# USB_RS485_Board.net
KiCad netlist of a schematic drawn in Altium Designer
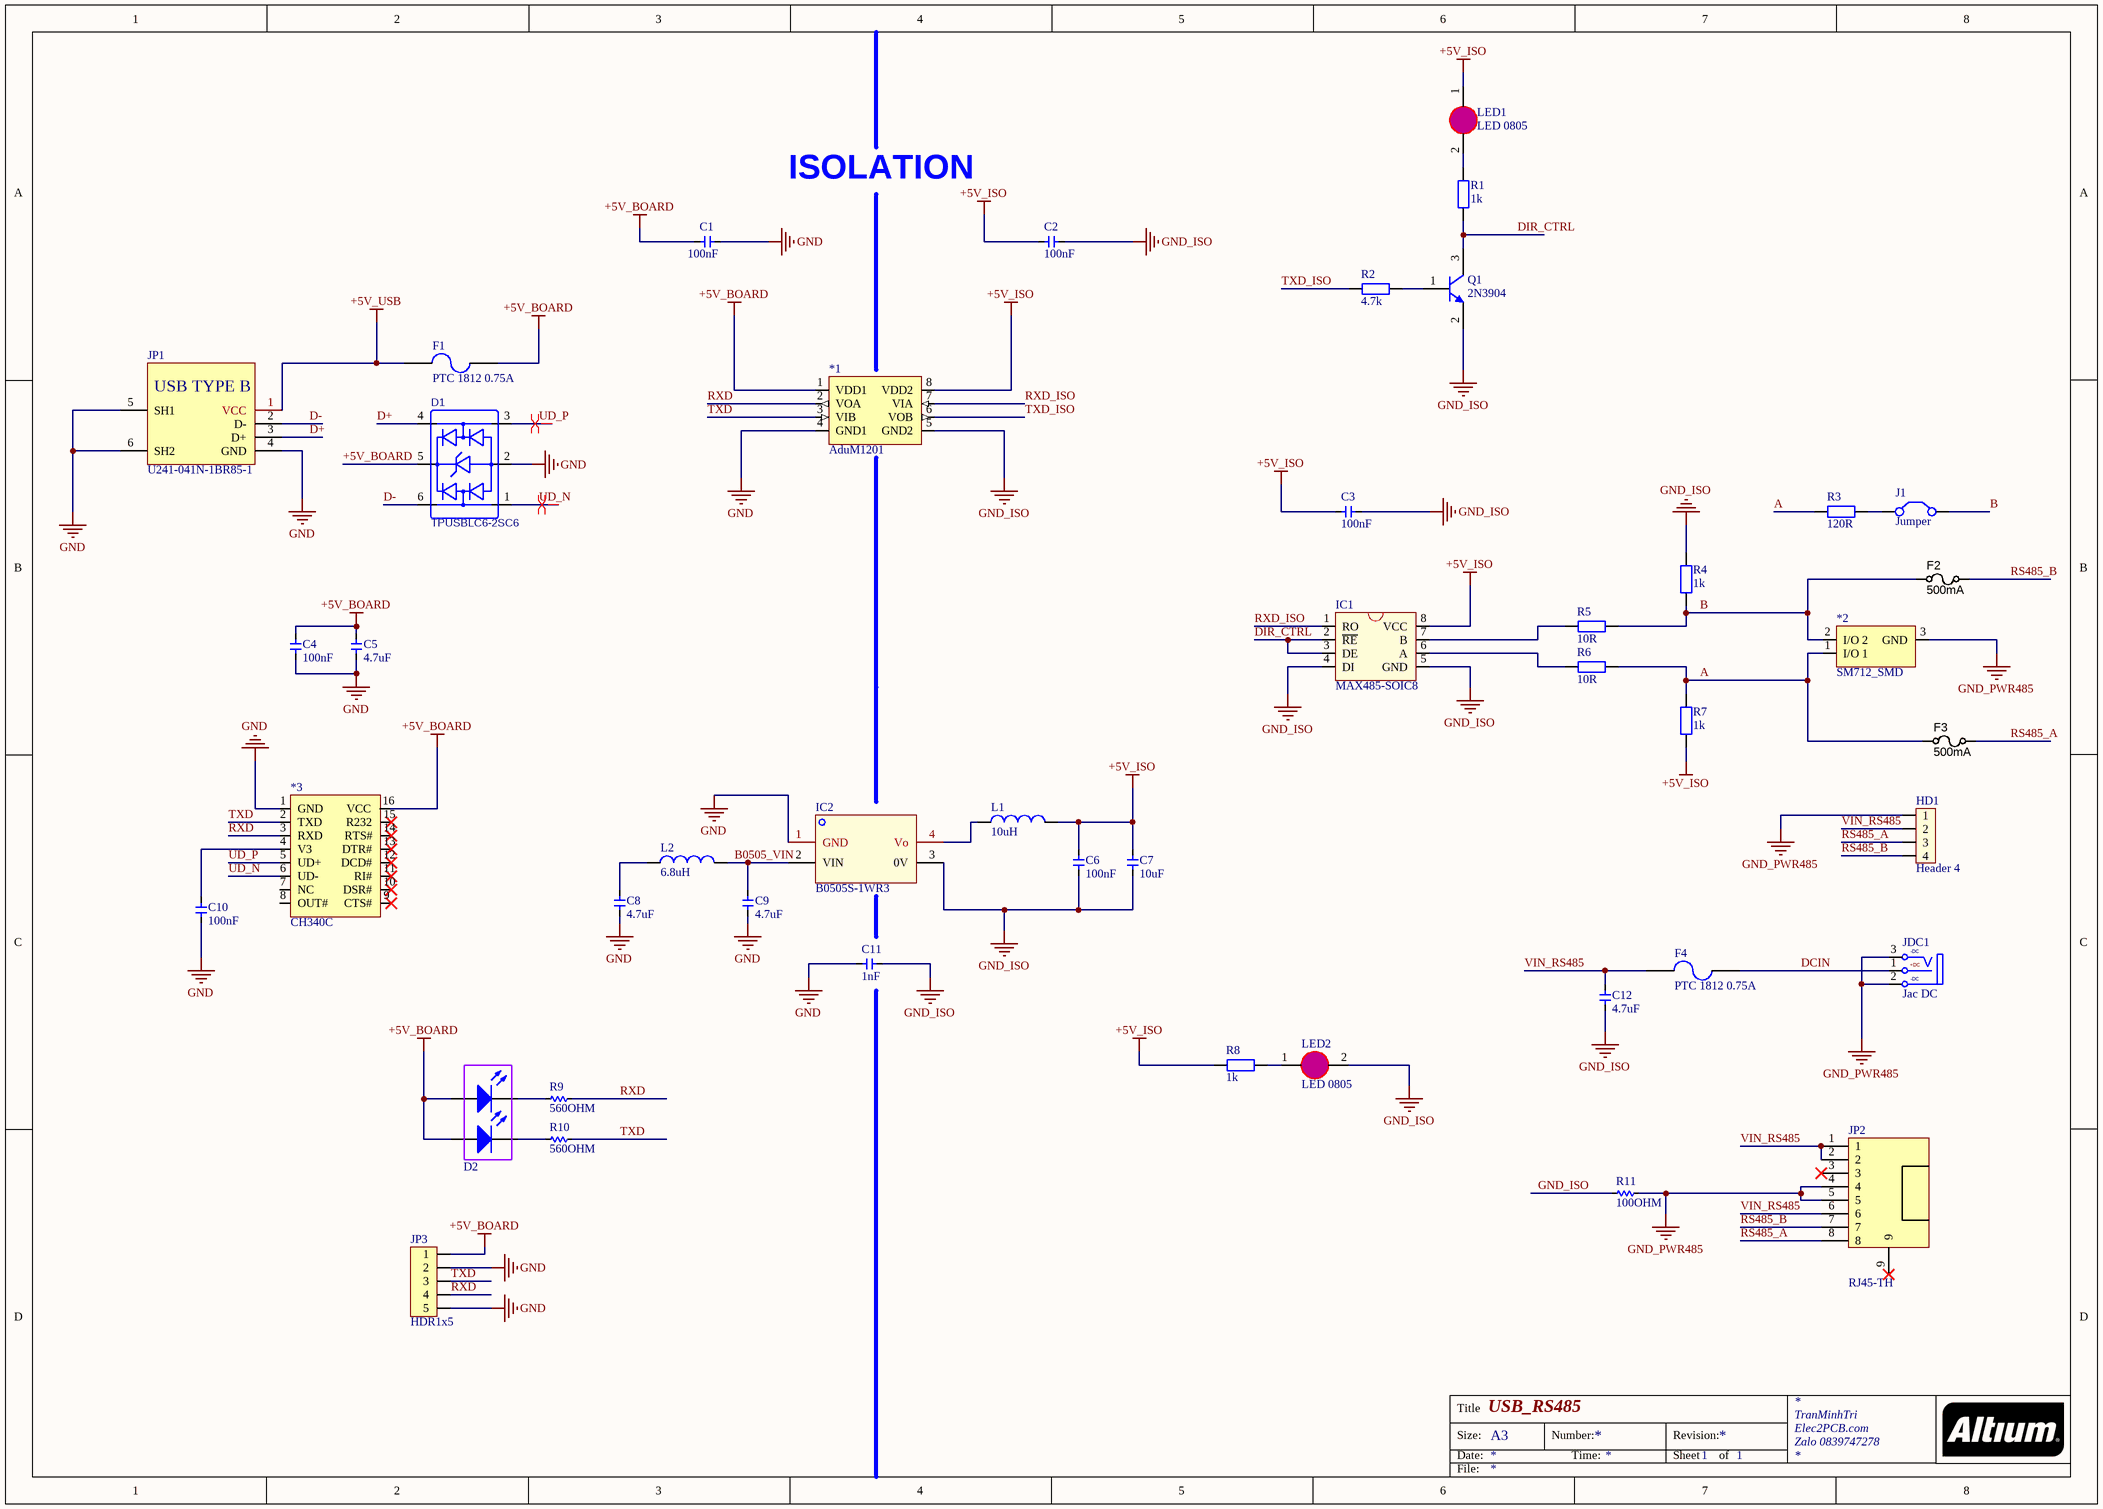
[diagram p0: USB_RS485_Board.SchDoc]

(export (version "E")
  (design (tool "Eeschema 10.0.6"))
  (components
    (comp (ref "*1")
      (value "AduM1201")
      (footprint "THU VIEN PCB:SO-8")
      (libsource (lib "lpson") (part "AduM1201"))
    )
    (comp (ref "*2")
      (value "SM712_SMD")
      (footprint "my Library:SOT23-3")
      (libsource (lib "lpson") (part "SM712_SMD"))
    )
    (comp (ref "*3")
      (value "CH340C")
      (footprint "THU VIEN PCB:SOP16")
      (libsource (lib "lpson") (part "CH340C dip"))
    )
    (comp (ref "C1")
      (value "100nF")
      (footprint "my Library:C_0603")
      (description "100nF 50V X7R ±10% 0603 Multilayer Ceramic Capacitors MLCC - SMD/SMT ROHS")
      (fields
        (field (name "MANUFACTURER") "YAGEO")
        (field (name "MANUFACTURER PART NUMBER") "CC0603KRX7R9BB104")
      )
      (libsource (lib "USB to RS485 ISO - ISO3088") (part "CC0603KRX7R9BB104"))
    )
    (comp (ref "C2")
      (value "100nF")
      (footprint "my Library:C_0603")
      (description "100nF 50V X7R ±10% 0603 Multilayer Ceramic Capacitors MLCC - SMD/SMT ROHS")
      (fields
        (field (name "MANUFACTURER") "YAGEO")
        (field (name "MANUFACTURER PART NUMBER") "CC0603KRX7R9BB104")
      )
      (libsource (lib "USB to RS485 ISO - ISO3088") (part "CC0603KRX7R9BB104"))
    )
    (comp (ref "C3")
      (value "100nF")
      (footprint "my Library:C_0603")
      (description "100nF 50V X7R ±10% 0603 Multilayer Ceramic Capacitors MLCC - SMD/SMT ROHS")
      (fields
        (field (name "MANUFACTURER") "YAGEO")
        (field (name "MANUFACTURER PART NUMBER") "CC0603KRX7R9BB104")
      )
      (libsource (lib "USB to RS485 ISO - ISO3088") (part "CC0603KRX7R9BB104"))
    )
    (comp (ref "C4")
      (value "100nF")
      (footprint "my Library:C_0603")
      (description "100nF 50V X7R ±10% 0603 Multilayer Ceramic Capacitors MLCC - SMD/SMT ROHS")
      (fields
        (field (name "MANUFACTURER") "YAGEO")
        (field (name "MANUFACTURER PART NUMBER") "CC0603KRX7R9BB104")
      )
      (libsource (lib "USB to RS485 ISO - ISO3088") (part "CC0603KRX7R9BB104"))
    )
    (comp (ref "C5")
      (value "4.7uF")
      (footprint "my Library:C_1206")
      (description "4.7uF 50V X7R ±10% 1206 Multilayer Ceramic Capacitors MLCC - SMD/SMT ROHS")
      (fields
        (field (name "MANUFACTURER") "FH(Guangdong Fenghua Advanced Tech)")
        (field (name "MANUFACTURER PART NUMBER") "1206B475K500NT")
      )
      (libsource (lib "USB to RS485 ISO - ISO3088") (part "1206B475K500NT"))
    )
    (comp (ref "C6")
      (value "100nF")
      (footprint "my Library:C_0603")
      (description "4.7uF 50V X7R ±10% 1206 Multilayer Ceramic Capacitors MLCC - SMD/SMT ROHS")
      (fields
        (field (name "MANUFACTURER") "FH(Guangdong Fenghua Advanced Tech)")
        (field (name "MANUFACTURER PART NUMBER") "1206B475K500NT")
      )
      (libsource (lib "USB to RS485 ISO - ISO3088") (part "1206B475K500NT"))
    )
    (comp (ref "C7")
      (value "10uF")
      (footprint "my Library:C_1206")
      (description "4.7uF 50V X7R ±10% 1206 Multilayer Ceramic Capacitors MLCC - SMD/SMT ROHS")
      (fields
        (field (name "MANUFACTURER") "FH(Guangdong Fenghua Advanced Tech)")
        (field (name "MANUFACTURER PART NUMBER") "1206B475K500NT")
      )
      (libsource (lib "USB to RS485 ISO - ISO3088") (part "1206B475K500NT"))
    )
    (comp (ref "C8")
      (value "4.7uF")
      (footprint "my Library:C_1206")
      (description "4.7uF 50V X7R ±10% 1206 Multilayer Ceramic Capacitors MLCC - SMD/SMT ROHS")
      (fields
        (field (name "MANUFACTURER") "FH(Guangdong Fenghua Advanced Tech)")
        (field (name "MANUFACTURER PART NUMBER") "1206B475K500NT")
      )
      (libsource (lib "USB to RS485 ISO - ISO3088") (part "1206B475K500NT"))
    )
    (comp (ref "C9")
      (value "4.7uF")
      (footprint "my Library:C_1206")
      (description "4.7uF 50V X7R ±10% 1206 Multilayer Ceramic Capacitors MLCC - SMD/SMT ROHS")
      (fields
        (field (name "MANUFACTURER") "FH(Guangdong Fenghua Advanced Tech)")
        (field (name "MANUFACTURER PART NUMBER") "1206B475K500NT")
      )
      (libsource (lib "USB to RS485 ISO - ISO3088") (part "1206B475K500NT"))
    )
    (comp (ref "C10")
      (value "100nF")
      (footprint "my Library:C_0603")
      (description "100nF 50V X7R ±10% 0603 Multilayer Ceramic Capacitors MLCC - SMD/SMT ROHS")
      (fields
        (field (name "MANUFACTURER") "YAGEO")
        (field (name "MANUFACTURER PART NUMBER") "CC0603KRX7R9BB104")
      )
      (libsource (lib "USB to RS485 ISO - ISO3088") (part "CC0603KRX7R9BB104"))
    )
    (comp (ref "C11")
      (value "1nF")
      (footprint "C_1206")
      (description "1nF ±5% 1kV NP0 1206 Multilayer Ceramic Capacitors MLCC - SMD/SMT RoHS")
      (fields
        (field (name "MANUFACTURER") "YAGEO")
        (field (name "MANUFACTURER PART NUMBER") "CC1206JKNPOCBN102")
      )
      (libsource (lib "USB to RS485 ISO - ISO3088") (part "CC1206JKNPOCBN102"))
    )
    (comp (ref "C12")
      (value "4.7uF")
      (footprint "my Library:C_1206")
      (description "4.7uF 50V X7R ±10% 1206 Multilayer Ceramic Capacitors MLCC - SMD/SMT ROHS")
      (fields
        (field (name "MANUFACTURER") "FH(Guangdong Fenghua Advanced Tech)")
        (field (name "MANUFACTURER PART NUMBER") "1206B475K500NT")
      )
      (libsource (lib "USB to RS485 ISO - ISO3088") (part "1206B475K500NT"))
    )
    (comp (ref "D1")
      (value "TPUSBLC6-2SC6")
      (footprint "my Library:SOT-23-6_L2.9-W1.6-P0.95-LS2.8-BR")
      (description "ESD ROHS SOT23-6 DIODES")
      (fields (field (name "LCSC PART NUMBER") "C558442") (field (name "MANUFACTURER") "TECH PUBLIC"))
      (libsource (lib "lpson") (part "ESD_TPUSBLC6-2SC6"))
    )
    (comp (ref "D2")
      (value "2LED_3MM")
      (footprint "my Library:2LED_3MM")
      (description "LED DUAL RED/GREEN DIFFUSED T/H")
      (fields (field (name "MANUFACTURER") "Lumex") (field (name "MANUFACTURER PART NUMBER") "SSF-LXH240IGD"))
      (libsource (lib "USB to RS485 ISO V1I0") (part "2LED3MM"))
    )
    (comp (ref "F1")
      (value "PTC 1812 0.75A")
      (footprint "Fuse_1812_smd")
      (description "1812 PTC RESETTABLE FUSES ROHS 24V")
      (fields
        (field (name "MANUFACTURER") "TECHFUSE")
        (field (name "MANUFACTURER PART NUMBER") "mSMD075-33V")
      )
      (libsource (lib "lpson") (part "Fuse_PTC_mSMD075-33V"))
    )
    (comp (ref "F2")
      (value "500mA")
      (footprint "my Library:FUSE-SM-1206")
      (description "Fuse 500mA 32VDC 0603 SMD")
      (fields (field (name "Comment") "Fast Acting"))
      (libsource (lib "My library altium") (part "FUSE_FAST_500mA_0603"))
    )
    (comp (ref "F3")
      (value "500mA")
      (footprint "my Library:FUSE-SM-1206")
      (description "Fuse 500mA 32VDC 0603 SMD")
      (fields (field (name "Comment") "Fast Acting"))
      (libsource (lib "My library altium") (part "FUSE_FAST_500mA_0603"))
    )
    (comp (ref "F4")
      (value "PTC 1812 0.75A")
      (footprint "my Library:Fuse_1812_smd")
      (description "1812 PTC RESETTABLE FUSES ROHS 24V")
      (fields
        (field (name "MANUFACTURER") "TECHFUSE")
        (field (name "MANUFACTURER PART NUMBER") "mSMD075-33V")
      )
      (libsource (lib "lpson") (part "Fuse_PTC_mSMD075-33V"))
    )
    (comp (ref "HD1")
      (value "Header 4")
      (footprint "Terminal plug 3.81_4P")
      (libsource (lib "lpson") (part "Header4"))
    )
    (comp (ref "IC1")
      (value "MAX485-SOIC8")
      (footprint "THU VIEN PCB:SO-8")
      (libsource (lib "lpson") (part "MAX485_1"))
    )
    (comp (ref "IC2")
      (value "B0505S-1WR3")
      (footprint "PWRM-TH_BXXXXS-1WR3")
      (description "B0505S-1WR3 5V 200mA 5.5V 1 Plugin Power Modules ROHS")
      (fields
        (field (name "MANUFACTURER") "MORNSUN Guangzhou S& T")
        (field (name "LCSC PART NUMBER") "C131038")
      )
      (libsource (lib "lpson") (part "B0505S-1WR3"))
    )
    (comp (ref "J1")
      (value "Jumper")
      (footprint "Header_2")
      (description "Jumper Wire")
      (fields (field (name "PUBLISHER") "Altium Limited"))
      (libsource (lib "lpson") (part "Jumper"))
    )
    (comp (ref "JDC1")
      (value "Jac DC")
      (footprint "DC0")
      (description "Jac DC input 5.5x2.1MM")
      (fields (field (name "MANUFACTURER PART NUMBER") "DC+02I") (field (name "LCSC PART NUMBER") "C718033"))
      (libsource (lib "USB to RS485 ISO V1I0") (part "DCIN_1"))
    )
    (comp (ref "JP1")
      (value "U241-041N-1BR85-1")
      (footprint "my Library:USB-B-TH_U241-041N-1BR85-1")
      (description "USB - Type B Female USB 2.0 4 Through Hole USB Connectors RoHS")
      (fields (field (name "LCSC PART NUMBER") "C397338") (field (name "MANUFACTURER") "XKB Connectivity"))
      (libsource (lib "my Library") (part "USB_TYPE_B_U241"))
    )
    (comp (ref "JP2")
      (value "RJ45-TH")
      (footprint "my Library:RJ45R10P-B000")
      (description "RJ45 18MM, No Transformer")
      (fields
        (field (name "MANUFACTURER") "Ckmtw(Shenzhen Cankemeng)")
        (field (name "LCSC PART NUMBER") "C386758")
      )
      (libsource (lib "USB to RS485 ISO V1I0") (part "RJ45R10P-B000"))
    )
    (comp (ref "JP3")
      (value "HDR1x5")
      (footprint "HDR1X5")
      (description "Header IDC, 5 x 1 Pin Vertical 2.54mm Pitch (Non-Boxed, Male)")
      (fields (field (name "LCSC PART NUMBER") "No"))
      (libsource (lib "USB to RS485 ISO V1I0") (part "Header5"))
    )
    (comp (ref "L1")
      (value "10uH")
      (footprint "my Library:IND-SMD_L4.0-W4.0")
      (description "6.8UH ±20% 980MA 247MΩ SMD,3.0X3.0X1.2MM POWER INDUCTORS ROHS")
      (fields
        (field (name "MANUFACTURER") "Sunlord")
        (field (name "MANUFACTURER PART NUMBER") "SWPA3012S6R8MT")
      )
      (libsource (lib "USB to RS485 ISO - ISO3088") (part "IND_SWP_6R8"))
    )
    (comp (ref "L2")
      (value "6.8uH")
      (footprint "IND-SMD_L4.0-W4.0")
      (description "6.8UH ±20% 980MA 247MΩ SMD,3.0X3.0X1.2MM POWER INDUCTORS ROHS")
      (fields
        (field (name "MANUFACTURER") "Sunlord")
        (field (name "MANUFACTURER PART NUMBER") "SWPA3012S6R8MT")
      )
      (libsource (lib "USB to RS485 ISO - ISO3088") (part "IND_SWP_6R8"))
    )
    (comp (ref "LED1")
      (value "LED 0805")
      (footprint "LED0805")
      (description "Dán")
      (libsource (lib "THU VIEN SCH") (part "LEDSMD"))
    )
    (comp (ref "LED2")
      (value "LED 0805")
      (footprint "LED0805")
      (description "Dán")
      (libsource (lib "THU VIEN SCH") (part "LEDSMD"))
    )
    (comp (ref "Q1")
      (value "2N3904")
      (footprint "17# 2SC1815-HF")
      (description "2SC1815 50V 150mA \r\nNPN SMD Transistor (No Pb, GP- Green Part)\r\nSOT-23 Package")
      (libsource (lib "lpson") (part "17#2SC1815-SOT23 SMD"))
    )
    (comp (ref "R1")
      (value "1k")
      (footprint "my Library:R_0805")
      (description "Dán")
      (libsource (lib "THU VIEN SCH") (part "Tro 0603 1% 1k"))
    )
    (comp (ref "R2")
      (value "4.7k")
      (footprint "R_0805")
      (description "Dán")
      (libsource (lib "THU VIEN SCH") (part "Tro 0603 1% 1k"))
    )
    (comp (ref "R3")
      (value "120R")
      (footprint "my Library:R_1206")
      (description "Dán")
      (libsource (lib "THU VIEN SCH") (part "Tro 0805 5% 120R"))
    )
    (comp (ref "R4")
      (value "1k")
      (footprint "my Library:R_1206")
      (description "Dán")
      (libsource (lib "THU VIEN SCH") (part "Tro 0805 5% 1k"))
    )
    (comp (ref "R5")
      (value "10R")
      (footprint "tro smd 1206")
      (description "Dán")
      (libsource (lib "THU VIEN SCH") (part "Tro 1206 5% 10R"))
    )
    (comp (ref "R6")
      (value "10R")
      (footprint "tro smd 1206")
      (description "Dán")
      (libsource (lib "THU VIEN SCH") (part "Tro 1206 5% 10R"))
    )
    (comp (ref "R7")
      (value "1k")
      (footprint "tro smd 1206")
      (description "Dán")
      (libsource (lib "THU VIEN SCH") (part "Tro 1206 5% 10R"))
    )
    (comp (ref "R8")
      (value "1k")
      (footprint "my Library:R_0805")
      (description "Dán")
      (libsource (lib "THU VIEN SCH") (part "Tro 0603 1% 1k"))
    )
    (comp (ref "R9")
      (value "560OHM")
      (footprint "my Library:R_0805")
      (description "560OHMS ±1% 1/10W 0603 ROHS")
      (fields
        (field (name "MANUFACTURER") "Uniroyal Elec")
        (field (name "MANUFACTURER PART NUMBER") "0603WAF5600T5E")
      )
      (libsource (lib "USB to RS485 ISO - ISO3088") (part "0603WAF5600T5E"))
    )
    (comp (ref "R10")
      (value "560OHM")
      (footprint "my Library:R_0805")
      (description "560OHMS ±1% 1/10W 0603 ROHS")
      (fields
        (field (name "MANUFACTURER") "Uniroyal Elec")
        (field (name "MANUFACTURER PART NUMBER") "0603WAF5600T5E")
      )
      (libsource (lib "USB to RS485 ISO - ISO3088") (part "0603WAF5600T5E"))
    )
    (comp (ref "R11")
      (value "100OHM")
      (footprint "my Library:R_1206")
      (description "100OHMS ±1% 1/8W 0805 ROHS")
      (fields
        (field (name "MANUFACTURER") "Uniroyal Elec")
        (field (name "MANUFACTURER PART NUMBER") "0805W8F1000T5E")
      )
      (libsource (lib "USB to RS485 ISO - ISO3088") (part "0805W8F1000T5E"))
    )
  )
  (nets
    (net (code "1") (name "+5V_BOARD") (class "Default")
      (node (ref "*1") (pin "1") (pinfunction "VDD1_1") (pintype "power_in"))
      (node (ref "*3") (pin "16") (pinfunction "VCC_16") (pintype "power_in"))
      (node (ref "C1") (pin "2") (pinfunction "2_2") (pintype "passive"))
      (node (ref "C4") (pin "2") (pinfunction "2_2") (pintype "passive"))
      (node (ref "C5") (pin "2") (pinfunction "2_2") (pintype "passive"))
      (node (ref "D1") (pin "5") (pinfunction "VBUS_5") (pintype "passive"))
      (node (ref "D2") (pin "1") (pinfunction "A_1") (pintype "passive"))
      (node (ref "D2") (pin "3") (pinfunction "A_3") (pintype "passive"))
      (node (ref "F1") (pin "2") (pinfunction "2_2") (pintype "passive"))
      (node (ref "JP3") (pin "1") (pinfunction "1_1") (pintype "passive"))
    )
    (net (code "2") (name "+5V_ISO") (class "Default")
      (node (ref "*1") (pin "8") (pinfunction "VDD2_8") (pintype "power_in"))
      (node (ref "C2") (pin "2") (pinfunction "2_2") (pintype "passive"))
      (node (ref "C3") (pin "2") (pinfunction "2_2") (pintype "passive"))
      (node (ref "C6") (pin "2") (pinfunction "2_2") (pintype "passive"))
      (node (ref "C7") (pin "2") (pinfunction "2_2") (pintype "passive"))
      (node (ref "IC1") (pin "8") (pinfunction "VCC_8") (pintype "passive"))
      (node (ref "L1") (pin "2") (pinfunction "2_2") (pintype "passive"))
      (node (ref "LED1") (pin "1") (pinfunction "A_1") (pintype "passive"))
      (node (ref "R7") (pin "1") (pinfunction "1_1") (pintype "passive"))
      (node (ref "R8") (pin "1") (pinfunction "1_1") (pintype "passive"))
    )
    (net (code "3") (name "+5V_USB") (class "Default")
      (node (ref "F1") (pin "1") (pinfunction "1_1") (pintype "passive"))
      (node (ref "JP1") (pin "1") (pinfunction "VCC_1") (pintype "power_in"))
    )
    (net (code "4") (name "/A") (class "Default")
      (node (ref "*2") (pin "1") (pinfunction "I/O_1_1") (pintype "bidirectional"))
      (node (ref "F3") (pin "1") (pinfunction "1_1") (pintype "passive"))
      (node (ref "R3") (pin "2") (pinfunction "2_2") (pintype "passive"))
      (node (ref "R6") (pin "2") (pinfunction "2_2") (pintype "passive"))
      (node (ref "R7") (pin "2") (pinfunction "2_2") (pintype "passive"))
    )
    (net (code "5") (name "/B") (class "Default")
      (node (ref "*2") (pin "2") (pinfunction "I/O_2_2") (pintype "bidirectional"))
      (node (ref "F2") (pin "1") (pinfunction "1_1") (pintype "passive"))
      (node (ref "J1") (pin "2") (pinfunction "C2_2") (pintype "passive"))
      (node (ref "R4") (pin "1") (pinfunction "1_1") (pintype "passive"))
      (node (ref "R5") (pin "2") (pinfunction "2_2") (pintype "passive"))
    )
    (net (code "6") (name "/B0505_VIN") (class "Default")
      (node (ref "C9") (pin "2") (pinfunction "2_2") (pintype "passive"))
      (node (ref "IC2") (pin "2") (pinfunction "VIN_2") (pintype "power_in"))
      (node (ref "L2") (pin "2") (pinfunction "2_2") (pintype "passive"))
    )
    (net (code "7") (name "/D+") (class "Default")
      (node (ref "D1") (pin "4") (pinfunction "I/O2_4") (pintype "passive"))
      (node (ref "JP1") (pin "3") (pinfunction "D+_3") (pintype "tri_state"))
    )
    (net (code "8") (name "/D-") (class "Default")
      (node (ref "D1") (pin "6") (pinfunction "I/O1_6") (pintype "passive"))
      (node (ref "JP1") (pin "2") (pinfunction "D-_2") (pintype "tri_state"))
    )
    (net (code "9") (name "/DCIN") (class "Default")
      (node (ref "F4") (pin "2") (pinfunction "2_2") (pintype "passive"))
      (node (ref "JDC1") (pin "1") (pinfunction "S_1") (pintype "power_in"))
    )
    (net (code "10") (name "/DIR_CTRL") (class "Default")
      (node (ref "IC1") (pin "2") (pinfunction "~{RE}_2") (pintype "passive"))
      (node (ref "IC1") (pin "3") (pinfunction "DE_3") (pintype "passive"))
      (node (ref "Q1") (pin "3") (pinfunction "C_3") (pintype "passive"))
      (node (ref "R1") (pin "1") (pinfunction "1_1") (pintype "passive"))
    )
    (net (code "11") (name "/RS485_A") (class "Default")
      (node (ref "F3") (pin "2") (pinfunction "2_2") (pintype "passive"))
      (node (ref "HD1") (pin "3") (pinfunction "3_3") (pintype "passive"))
      (node (ref "JP2") (pin "8") (pinfunction "8_8") (pintype "passive"))
    )
    (net (code "12") (name "/RS485_B") (class "Default")
      (node (ref "F2") (pin "2") (pinfunction "2_2") (pintype "passive"))
      (node (ref "HD1") (pin "4") (pinfunction "4_4") (pintype "passive"))
      (node (ref "JP2") (pin "7") (pinfunction "7_7") (pintype "passive"))
    )
    (net (code "13") (name "/RXD") (class "Default")
      (node (ref "*1") (pin "2") (pinfunction "VOA_2") (pintype "output"))
      (node (ref "*3") (pin "3") (pinfunction "RXD_3") (pintype "input"))
      (node (ref "JP3") (pin "4") (pinfunction "4_4") (pintype "passive"))
      (node (ref "R9") (pin "1") (pinfunction "1_1") (pintype "passive"))
    )
    (net (code "14") (name "/RXD_ISO") (class "Default")
      (node (ref "*1") (pin "7") (pinfunction "VIA_7") (pintype "input"))
      (node (ref "IC1") (pin "1") (pinfunction "RO_1") (pintype "passive"))
    )
    (net (code "15") (name "/TXD") (class "Default")
      (node (ref "*1") (pin "3") (pinfunction "VIB_3") (pintype "input"))
      (node (ref "*3") (pin "2") (pinfunction "TXD_2") (pintype "output"))
      (node (ref "JP3") (pin "3") (pinfunction "3_3") (pintype "passive"))
      (node (ref "R10") (pin "1") (pinfunction "1_1") (pintype "passive"))
    )
    (net (code "16") (name "/TXD_ISO") (class "Default")
      (node (ref "*1") (pin "6") (pinfunction "VOB_6") (pintype "output"))
      (node (ref "R2") (pin "1") (pinfunction "1_1") (pintype "passive"))
    )
    (net (code "17") (name "/UD_N") (class "Default")
      (node (ref "*3") (pin "6") (pinfunction "UD-_6") (pintype "bidirectional"))
      (node (ref "D1") (pin "1") (pinfunction "I/O1_1") (pintype "passive"))
    )
    (net (code "18") (name "/UD_P") (class "Default")
      (node (ref "*3") (pin "5") (pinfunction "UD+_5") (pintype "bidirectional"))
      (node (ref "D1") (pin "3") (pinfunction "I/O2_3") (pintype "passive"))
    )
    (net (code "19") (name "/VIN_RS485") (class "Default")
      (node (ref "C12") (pin "2") (pinfunction "2_2") (pintype "passive"))
      (node (ref "F4") (pin "1") (pinfunction "1_1") (pintype "passive"))
      (node (ref "HD1") (pin "2") (pinfunction "2_2") (pintype "passive"))
      (node (ref "JP2") (pin "1") (pinfunction "1_1") (pintype "passive"))
      (node (ref "JP2") (pin "2") (pinfunction "2_2") (pintype "passive"))
      (node (ref "JP2") (pin "6") (pinfunction "6_6") (pintype "passive"))
    )
    (net (code "20") (name "GND") (class "Default")
      (node (ref "*1") (pin "4") (pinfunction "GND1_4") (pintype "power_in"))
      (node (ref "*3") (pin "1") (pinfunction "GND_1") (pintype "power_in"))
      (node (ref "C1") (pin "1") (pinfunction "1_1") (pintype "passive"))
      (node (ref "C10") (pin "1") (pinfunction "1_1") (pintype "passive"))
      (node (ref "C11") (pin "1") (pinfunction "1_1") (pintype "passive"))
      (node (ref "C4") (pin "1") (pinfunction "1_1") (pintype "passive"))
      (node (ref "C5") (pin "1") (pinfunction "1_1") (pintype "passive"))
      (node (ref "C8") (pin "1") (pinfunction "1_1") (pintype "passive"))
      (node (ref "C9") (pin "1") (pinfunction "1_1") (pintype "passive"))
      (node (ref "D1") (pin "2") (pinfunction "GND_2") (pintype "passive"))
      (node (ref "IC2") (pin "1") (pinfunction "GND_1") (pintype "power_in"))
      (node (ref "JP1") (pin "4") (pinfunction "GND_4") (pintype "power_in"))
      (node (ref "JP1") (pin "5") (pinfunction "SH1_5") (pintype "passive"))
      (node (ref "JP1") (pin "6") (pinfunction "SH2_6") (pintype "passive"))
      (node (ref "JP3") (pin "2") (pinfunction "2_2") (pintype "passive"))
      (node (ref "JP3") (pin "5") (pinfunction "5_5") (pintype "passive"))
    )
    (net (code "21") (name "GND_ISO") (class "Default")
      (node (ref "*1") (pin "5") (pinfunction "GND2_5") (pintype "power_in"))
      (node (ref "C11") (pin "2") (pinfunction "2_2") (pintype "passive"))
      (node (ref "C12") (pin "1") (pinfunction "1_1") (pintype "passive"))
      (node (ref "C2") (pin "1") (pinfunction "1_1") (pintype "passive"))
      (node (ref "C3") (pin "1") (pinfunction "1_1") (pintype "passive"))
      (node (ref "C6") (pin "1") (pinfunction "1_1") (pintype "passive"))
      (node (ref "C7") (pin "1") (pinfunction "1_1") (pintype "passive"))
      (node (ref "IC1") (pin "4") (pinfunction "DI_4") (pintype "passive"))
      (node (ref "IC1") (pin "5") (pinfunction "GND_5") (pintype "passive"))
      (node (ref "IC2") (pin "3") (pinfunction "0V_3") (pintype "power_in"))
      (node (ref "LED2") (pin "2") (pinfunction "K_2") (pintype "passive"))
      (node (ref "Q1") (pin "2") (pinfunction "E_2") (pintype "passive"))
      (node (ref "R11") (pin "2") (pinfunction "2_2") (pintype "passive"))
      (node (ref "R4") (pin "2") (pinfunction "2_2") (pintype "passive"))
    )
    (net (code "22") (name "GND_PWR485") (class "Default")
      (node (ref "*2") (pin "3") (pinfunction "GND_3") (pintype "power_in"))
      (node (ref "HD1") (pin "1") (pinfunction "1_1") (pintype "passive"))
      (node (ref "JDC1") (pin "2") (pinfunction "T_2") (pintype "passive"))
      (node (ref "JDC1") (pin "3") (pinfunction "TN_3") (pintype "passive"))
      (node (ref "JP2") (pin "4") (pinfunction "4_4") (pintype "passive"))
      (node (ref "JP2") (pin "5") (pinfunction "5_5") (pintype "passive"))
      (node (ref "R11") (pin "1") (pinfunction "1_1") (pintype "passive"))
    )
    (net (code "23") (name "Net-(*3-V3)") (class "Default")
      (node (ref "*3") (pin "4") (pinfunction "V3_4") (pintype "power_in"))
      (node (ref "C10") (pin "2") (pinfunction "2_2") (pintype "passive"))
    )
    (net (code "24") (name "Net-(C8-Pad2)") (class "Default")
      (node (ref "C8") (pin "2") (pinfunction "2_2") (pintype "passive"))
      (node (ref "L2") (pin "1") (pinfunction "1_1") (pintype "passive"))
    )
    (net (code "25") (name "Net-(D2-K-Pad2)") (class "Default")
      (node (ref "D2") (pin "2") (pinfunction "K_2") (pintype "passive"))
      (node (ref "R10") (pin "2") (pinfunction "2_2") (pintype "passive"))
    )
    (net (code "26") (name "Net-(D2-K-Pad4)") (class "Default")
      (node (ref "D2") (pin "4") (pinfunction "K_4") (pintype "passive"))
      (node (ref "R9") (pin "2") (pinfunction "2_2") (pintype "passive"))
    )
    (net (code "27") (name "Net-(IC1-A)") (class "Default")
      (node (ref "IC1") (pin "6") (pinfunction "A_6") (pintype "passive"))
      (node (ref "R6") (pin "1") (pinfunction "1_1") (pintype "passive"))
    )
    (net (code "28") (name "Net-(IC1-B)") (class "Default")
      (node (ref "IC1") (pin "7") (pinfunction "B_7") (pintype "passive"))
      (node (ref "R5") (pin "1") (pinfunction "1_1") (pintype "passive"))
    )
    (net (code "29") (name "Net-(IC2-Vo)") (class "Default")
      (node (ref "IC2") (pin "4") (pinfunction "Vo_4") (pintype "power_in"))
      (node (ref "L1") (pin "1") (pinfunction "1_1") (pintype "passive"))
    )
    (net (code "30") (name "Net-(J1-C1)") (class "Default")
      (node (ref "J1") (pin "1") (pinfunction "C1_1") (pintype "passive"))
      (node (ref "R3") (pin "1") (pinfunction "1_1") (pintype "passive"))
    )
    (net (code "31") (name "Net-(LED1-K)") (class "Default")
      (node (ref "LED1") (pin "2") (pinfunction "K_2") (pintype "passive"))
      (node (ref "R1") (pin "2") (pinfunction "2_2") (pintype "passive"))
    )
    (net (code "32") (name "Net-(LED2-A)") (class "Default")
      (node (ref "LED2") (pin "1") (pinfunction "A_1") (pintype "passive"))
      (node (ref "R8") (pin "2") (pinfunction "2_2") (pintype "passive"))
    )
    (net (code "33") (name "Net-(Q1-B)") (class "Default")
      (node (ref "Q1") (pin "1") (pinfunction "B_1") (pintype "passive"))
      (node (ref "R2") (pin "2") (pinfunction "2_2") (pintype "passive"))
    )
    (net (code "34") (name "unconnected-(*3-CTS#-Pad9)") (class "Default")
      (node (ref "*3") (pin "9") (pinfunction "CTS#_9") (pintype "input+no_connect"))
    )
    (net (code "35") (name "unconnected-(*3-DCD#-Pad12)") (class "Default")
      (node (ref "*3") (pin "12") (pinfunction "DCD#_12") (pintype "input+no_connect"))
    )
    (net (code "36") (name "unconnected-(*3-DSR#-Pad10)") (class "Default")
      (node (ref "*3") (pin "10") (pinfunction "DSR#_10") (pintype "input+no_connect"))
    )
    (net (code "37") (name "unconnected-(*3-DTR#-Pad13)") (class "Default")
      (node (ref "*3") (pin "13") (pinfunction "DTR#_13") (pintype "output+no_connect"))
    )
    (net (code "38") (name "unconnected-(*3-NC-Pad7)") (class "Default")
      (node (ref "*3") (pin "7") (pinfunction "NC_7") (pintype "passive"))
    )
    (net (code "39") (name "unconnected-(*3-OUT#-Pad8)") (class "Default")
      (node (ref "*3") (pin "8") (pinfunction "OUT#_8") (pintype "output"))
    )
    (net (code "40") (name "unconnected-(*3-R232-Pad15)") (class "Default")
      (node (ref "*3") (pin "15") (pinfunction "R232_15") (pintype "input+no_connect"))
    )
    (net (code "41") (name "unconnected-(*3-RI#-Pad11)") (class "Default")
      (node (ref "*3") (pin "11") (pinfunction "RI#_11") (pintype "input+no_connect"))
    )
    (net (code "42") (name "unconnected-(*3-RTS#-Pad14)") (class "Default")
      (node (ref "*3") (pin "14") (pinfunction "RTS#_14") (pintype "output+no_connect"))
    )
    (net (code "43") (name "unconnected-(JP2-Pad3)") (class "Default")
      (node (ref "JP2") (pin "3") (pinfunction "3_3") (pintype "passive+no_connect"))
    )
    (net (code "44") (name "unconnected-(JP2-Pad9)") (class "Default")
      (node (ref "JP2") (pin "9") (pinfunction "9_9") (pintype "passive+no_connect"))
    )
  )
)
